# ramp_generator.net
KiCad netlist of a schematic drawn in Altium Designer
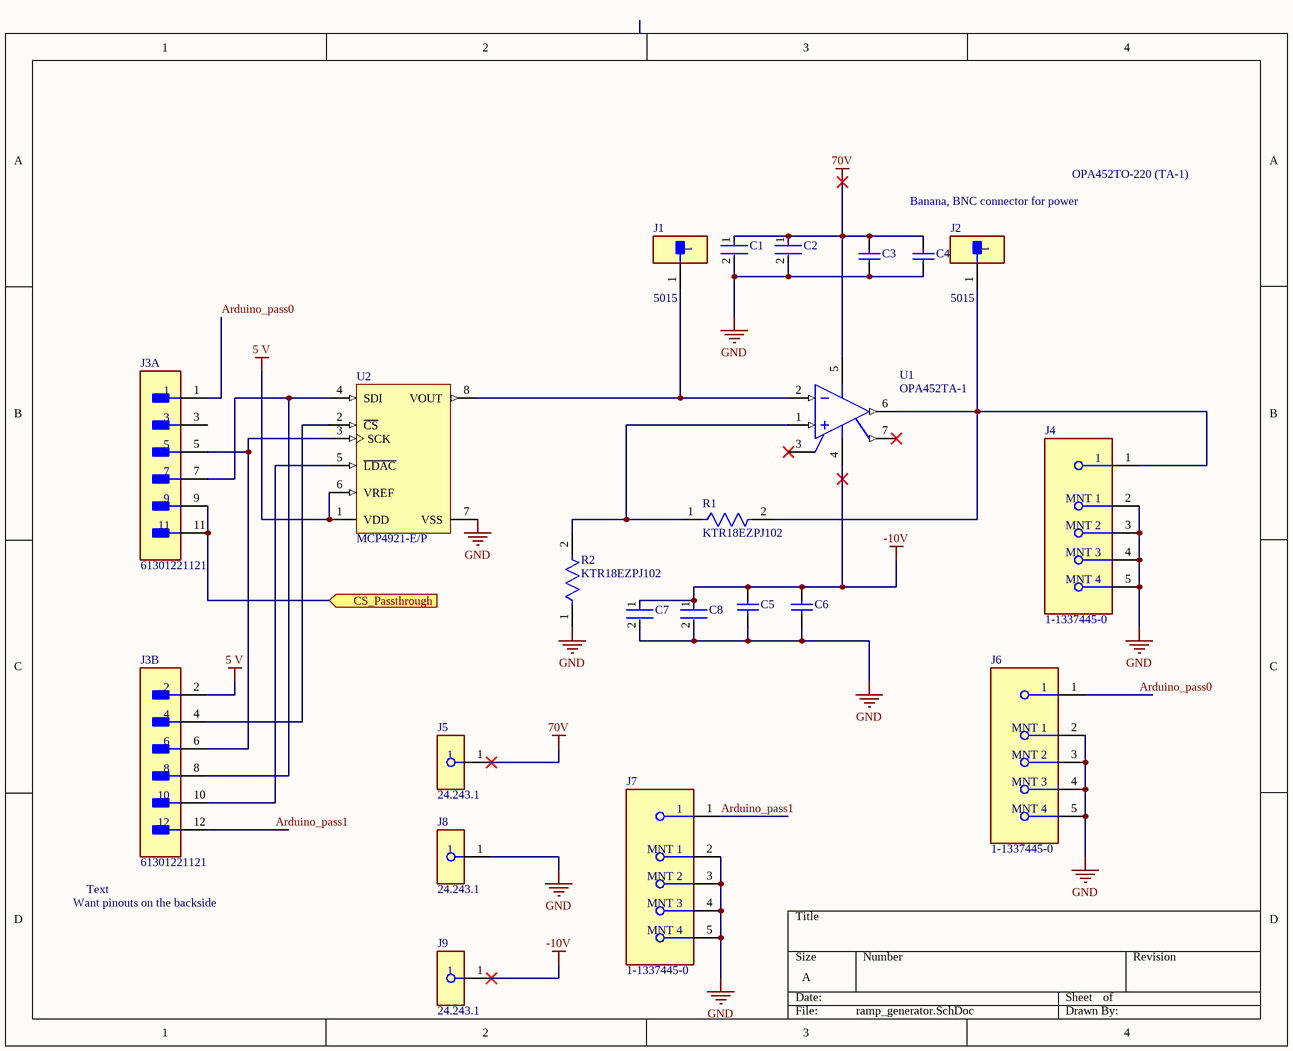
[diagram p0: ramp_generator.SchDoc]

(export (version "E")
  (design (tool "Eeschema 10.0.6"))
  (components
    (comp (ref "C1")
      (value "C3216JB1A106M160AA")
      (footprint "FP-C3216-160-0_2-IPC_C")
      (description "Multilayer Ceramic Capacitors 10uF ±20% 10V JB SMD 1206")
      (fields (field (name "TOLERANCE") "20%"))
      (libsource (lib "Altium Content Vault") (part "11868f565c42a9108669ba33697ecf6"))
    )
    (comp (ref "C2")
      (value "C3216JB1A106M160AA")
      (footprint "FP-C3216-160-0_2-IPC_C")
      (description "Multilayer Ceramic Capacitors 10uF ±20% 10V JB SMD 1206")
      (fields (field (name "TOLERANCE") "20%"))
      (libsource (lib "Altium Content Vault") (part "11868f565c42a9108669ba33697ecf6"))
    )
    (comp (ref "C3")
      (value "CAP 100pF 100V 1206(3216)")
      (footprint "CAPC1206(3216)100_N")
      (description "CAP 100pF 100V ±1% 1206 (3216 Metric) Thickness 1mm SMD")
      (fields (field (name "TOLERANCE") "Â±1%"))
      (libsource (lib "Altium Content Vault") (part "CAP"))
    )
    (comp (ref "C4")
      (value "CAP 100pF 100V 1206(3216)")
      (footprint "CAPC1206(3216)100_N")
      (description "CAP 100pF 100V ±1% 1206 (3216 Metric) Thickness 1mm SMD")
      (fields (field (name "TOLERANCE") "Â±1%"))
      (libsource (lib "Altium Content Vault") (part "CAP"))
    )
    (comp (ref "C5")
      (value "CAP 100pF 100V 1206(3216)")
      (footprint "CAPC1206(3216)100_N")
      (description "CAP 100pF 100V ±1% 1206 (3216 Metric) Thickness 1mm SMD")
      (fields (field (name "TOLERANCE") "Â±1%"))
      (libsource (lib "Altium Content Vault") (part "CAP"))
    )
    (comp (ref "C6")
      (value "CAP 100pF 100V 1206(3216)")
      (footprint "CAPC1206(3216)100_N")
      (description "CAP 100pF 100V ±1% 1206 (3216 Metric) Thickness 1mm SMD")
      (fields (field (name "TOLERANCE") "Â±1%"))
      (libsource (lib "Altium Content Vault") (part "CAP"))
    )
    (comp (ref "C7")
      (value "C3216JB1A106M160AA")
      (footprint "FP-C3216-160-0_2-IPC_C")
      (description "Multilayer Ceramic Capacitors 10uF ±20% 10V JB SMD 1206")
      (fields (field (name "TOLERANCE") "20%"))
      (libsource (lib "Altium Content Vault") (part "11868f565c42a9108669ba33697ecf6"))
    )
    (comp (ref "C8")
      (value "C3216JB1A106M160AA")
      (footprint "FP-C3216-160-0_2-IPC_C")
      (description "Multilayer Ceramic Capacitors 10uF ±20% 10V JB SMD 1206")
      (fields (field (name "TOLERANCE") "20%"))
      (libsource (lib "Altium Content Vault") (part "11868f565c42a9108669ba33697ecf6"))
    )
    (comp (ref "J1")
      (value "5015")
      (footprint "FP-5015-MFG")
      (description "PC TEST POINT MINIATURE")
      (fields
        (field (name "MANUFACTURER") "keystone")
        (field (name "OCTOPART") "https://octopart.com/5015-keystone-3822")
      )
      (libsource (lib "Altium Content Vault") (part "dd45045ce8184df9e99e12baf3f412c"))
    )
    (comp (ref "J2")
      (value "5015")
      (footprint "FP-5015-MFG")
      (description "PC TEST POINT MINIATURE")
      (fields
        (field (name "MANUFACTURER") "keystone")
        (field (name "OCTOPART") "https://octopart.com/5015-keystone-3822")
      )
      (libsource (lib "Altium Content Vault") (part "dd45045ce8184df9e99e12baf3f412c"))
    )
    (comp (ref "J3")
      (value "61301221121")
      (footprint "FP-61301221121-MFG")
      (description "CONN HEADER VERT 12POS 2.54MM")
      (libsource (lib "Altium Content Vault") (part "803cea653fbe7ecf087c1bc3cef566d"))
    )
    (comp (ref "J4")
      (value "1-1337445-0")
      (footprint "FP-1-1337445-0-MFG")
      (description "CONN BNC JACK STR 50 OHM PCB")
      (libsource (lib "Altium Content Vault") (part "c65b8a639cdaef1819ea20b5466f8fa"))
    )
    (comp (ref "J5")
      (value "24.243.1")
      (footprint "FP-24_243_1-MFG")
      (description "Banana Test Connector, 4mm, Socket, PCB Mount, 24 A, 60 VDC, Silver Plated Contacts, Green")
      (libsource (lib "Altium Content Vault") (part "98815daf2f2c152b0c43f5ab9800df6"))
    )
    (comp (ref "J6")
      (value "1-1337445-0")
      (footprint "FP-1-1337445-0-MFG")
      (description "CONN BNC JACK STR 50 OHM PCB")
      (libsource (lib "Altium Content Vault") (part "c65b8a639cdaef1819ea20b5466f8fa"))
    )
    (comp (ref "J7")
      (value "1-1337445-0")
      (footprint "FP-1-1337445-0-MFG")
      (description "CONN BNC JACK STR 50 OHM PCB")
      (libsource (lib "Altium Content Vault") (part "c65b8a639cdaef1819ea20b5466f8fa"))
    )
    (comp (ref "J8")
      (value "24.243.1")
      (footprint "FP-24_243_1-MFG")
      (description "Banana Test Connector, 4mm, Socket, PCB Mount, 24 A, 60 VDC, Silver Plated Contacts, Green")
      (libsource (lib "Altium Content Vault") (part "98815daf2f2c152b0c43f5ab9800df6"))
    )
    (comp (ref "J9")
      (value "24.243.1")
      (footprint "FP-24_243_1-MFG")
      (description "Banana Test Connector, 4mm, Socket, PCB Mount, 24 A, 60 VDC, Silver Plated Contacts, Green")
      (libsource (lib "Altium Content Vault") (part "98815daf2f2c152b0c43f5ab9800df6"))
    )
    (comp (ref "R1")
      (value "KTR18EZPJ102")
      (footprint "FP-KTR18-IPC_A")
      (description "Res Thick Film 1206 1kΩ 5% 0.1W ±200ppm/°C Automotive Paper T/R")
      (fields (field (name "TOLERANCE") "5%"))
      (libsource (lib "Altium Content Vault") (part "1029c3af85768c4190bb7ad29bc67b5"))
    )
    (comp (ref "R2")
      (value "KTR18EZPJ102")
      (footprint "FP-KTR18-IPC_A")
      (description "Res Thick Film 1206 1kΩ 5% 0.1W ±200ppm/°C Automotive Paper T/R")
      (fields (field (name "TOLERANCE") "5%"))
      (libsource (lib "Altium Content Vault") (part "1029c3af85768c4190bb7ad29bc67b5"))
    )
    (comp (ref "U1")
      (value "OPA452TA-1")
      (footprint "KVT0007A")
      (description "Operational Amplifier, 20 to 80 V, -40 to 125 degC, 7-pin FM (KVT7), Green (RoHS & no Sb/Br)")
      (fields (field (name "MANUFACTURER") "Texas Instruments"))
      (libsource (lib "Altium Content Vault") (part "TI-OPA452_453-7"))
    )
    (comp (ref "U2")
      (value "MCP4921-E/P")
      (footprint "PDIP300-P8")
      (description "12-Bit DAC with SPI Interface, 8-Pin PDIP, Extended Temperature")
      (libsource (lib "Altium Content Vault") (part "CON-DAC-MCP4921-8"))
    )
  )
  (nets
    (net (code "1") (name "-10V") (class "Default")
      (node (ref "C5") (pin "2") (pinfunction "2_2") (pintype "passive"))
      (node (ref "C6") (pin "1") (pinfunction "1_1") (pintype "passive"))
      (node (ref "C7") (pin "1") (pinfunction "1_1") (pintype "passive"))
      (node (ref "C8") (pin "1") (pinfunction "1_1") (pintype "passive"))
      (node (ref "J9") (pin "1") (pinfunction "1_1") (pintype "passive"))
      (node (ref "U1") (pin "4") (pinfunction "V-_4") (pintype "power_in"))
    )
    (net (code "2") (name "/Arduino_pass0") (class "Default")
      (node (ref "J3") (pin "1") (pinfunction "1_1") (pintype "passive"))
      (node (ref "J6") (pin "1") (pinfunction "1_1") (pintype "passive"))
    )
    (net (code "3") (name "/Arduino_pass1") (class "Default")
      (node (ref "J3") (pin "12") (pinfunction "12_12") (pintype "passive"))
      (node (ref "J7") (pin "1") (pinfunction "1_1") (pintype "passive"))
    )
    (net (code "4") (name "/CS_Passthrough") (class "Default")
      (node (ref "J3") (pin "11") (pinfunction "11_11") (pintype "passive"))
      (node (ref "J3") (pin "9") (pinfunction "9_9") (pintype "passive"))
    )
    (net (code "5") (name "5 V") (class "Default")
      (node (ref "J3") (pin "2") (pinfunction "2_2") (pintype "passive"))
      (node (ref "U2") (pin "1") (pinfunction "VDD_1") (pintype "power_in"))
      (node (ref "U2") (pin "6") (pinfunction "VREF_6") (pintype "input"))
    )
    (net (code "6") (name "70V") (class "Default")
      (node (ref "C1") (pin "1") (pinfunction "1_1") (pintype "passive"))
      (node (ref "C2") (pin "1") (pinfunction "1_1") (pintype "passive"))
      (node (ref "C3") (pin "2") (pinfunction "2_2") (pintype "passive"))
      (node (ref "C4") (pin "2") (pinfunction "2_2") (pintype "passive"))
      (node (ref "J5") (pin "1") (pinfunction "1_1") (pintype "passive"))
      (node (ref "U1") (pin "5") (pinfunction "V+_5") (pintype "power_in"))
    )
    (net (code "7") (name "GND") (class "Default")
      (node (ref "C1") (pin "2") (pinfunction "2_2") (pintype "passive"))
      (node (ref "C2") (pin "2") (pinfunction "2_2") (pintype "passive"))
      (node (ref "C3") (pin "1") (pinfunction "1_1") (pintype "passive"))
      (node (ref "C4") (pin "1") (pinfunction "1_1") (pintype "passive"))
      (node (ref "C5") (pin "1") (pinfunction "1_1") (pintype "passive"))
      (node (ref "C6") (pin "2") (pinfunction "2_2") (pintype "passive"))
      (node (ref "C7") (pin "2") (pinfunction "2_2") (pintype "passive"))
      (node (ref "C8") (pin "2") (pinfunction "2_2") (pintype "passive"))
      (node (ref "J4") (pin "2") (pinfunction "MNT_1_2") (pintype "passive"))
      (node (ref "J4") (pin "3") (pinfunction "MNT_2_3") (pintype "passive"))
      (node (ref "J4") (pin "4") (pinfunction "MNT_3_4") (pintype "passive"))
      (node (ref "J4") (pin "5") (pinfunction "MNT_4_5") (pintype "passive"))
      (node (ref "J6") (pin "2") (pinfunction "MNT_1_2") (pintype "passive"))
      (node (ref "J6") (pin "3") (pinfunction "MNT_2_3") (pintype "passive"))
      (node (ref "J6") (pin "4") (pinfunction "MNT_3_4") (pintype "passive"))
      (node (ref "J6") (pin "5") (pinfunction "MNT_4_5") (pintype "passive"))
      (node (ref "J7") (pin "2") (pinfunction "MNT_1_2") (pintype "passive"))
      (node (ref "J7") (pin "3") (pinfunction "MNT_2_3") (pintype "passive"))
      (node (ref "J7") (pin "4") (pinfunction "MNT_3_4") (pintype "passive"))
      (node (ref "J7") (pin "5") (pinfunction "MNT_4_5") (pintype "passive"))
      (node (ref "J8") (pin "1") (pinfunction "1_1") (pintype "passive"))
      (node (ref "R2") (pin "1") (pinfunction "1_1") (pintype "passive"))
      (node (ref "U2") (pin "7") (pinfunction "VSS_7") (pintype "power_in"))
    )
    (net (code "8") (name "Net-(U1-VIN+)") (class "Default")
      (node (ref "R1") (pin "1") (pinfunction "1_1") (pintype "passive"))
      (node (ref "R2") (pin "2") (pinfunction "2_2") (pintype "passive"))
      (node (ref "U1") (pin "1") (pinfunction "VIN+_1") (pintype "input"))
    )
    (net (code "9") (name "Net-(U1-VIN-)") (class "Default")
      (node (ref "J1") (pin "1") (pinfunction "1_1") (pintype "passive"))
      (node (ref "U1") (pin "2") (pinfunction "VIN-_2") (pintype "input"))
      (node (ref "U2") (pin "8") (pinfunction "VOUT_8") (pintype "output"))
    )
    (net (code "10") (name "Net-(U1-VO)") (class "Default")
      (node (ref "J2") (pin "1") (pinfunction "1_1") (pintype "passive"))
      (node (ref "J4") (pin "1") (pinfunction "1_1") (pintype "passive"))
      (node (ref "R1") (pin "2") (pinfunction "2_2") (pintype "passive"))
      (node (ref "U1") (pin "6") (pinfunction "VO_6") (pintype "output"))
    )
    (net (code "11") (name "Net-(U2-SCK)") (class "Default")
      (node (ref "J3") (pin "5") (pinfunction "5_5") (pintype "passive"))
      (node (ref "J3") (pin "6") (pinfunction "6_6") (pintype "passive"))
      (node (ref "U2") (pin "3") (pinfunction "SCK_3") (pintype "input"))
    )
    (net (code "12") (name "Net-(U2-SDI)") (class "Default")
      (node (ref "J3") (pin "7") (pinfunction "7_7") (pintype "passive"))
      (node (ref "J3") (pin "8") (pinfunction "8_8") (pintype "passive"))
      (node (ref "U2") (pin "4") (pinfunction "SDI_4") (pintype "input"))
    )
    (net (code "13") (name "Net-(U2-~{CS})") (class "Default")
      (node (ref "J3") (pin "4") (pinfunction "4_4") (pintype "passive"))
      (node (ref "U2") (pin "2") (pinfunction "~{CS}_2") (pintype "input"))
    )
    (net (code "14") (name "Net-(U2-~{LDAC})") (class "Default")
      (node (ref "J3") (pin "10") (pinfunction "10_10") (pintype "passive"))
      (node (ref "U2") (pin "5") (pinfunction "~{LDAC}_5") (pintype "input"))
    )
    (net (code "15") (name "unconnected-(J3-Pad3)") (class "Default")
      (node (ref "J3") (pin "3") (pinfunction "3_3") (pintype "passive"))
    )
    (net (code "16") (name "unconnected-(U1-FLAG-Pad7)") (class "Default")
      (node (ref "U1") (pin "7") (pinfunction "FLAG_7") (pintype "output+no_connect"))
    )
    (net (code "17") (name "unconnected-(U1-NC-Pad3)") (class "Default")
      (node (ref "U1") (pin "3") (pinfunction "NC_3") (pintype "passive+no_connect"))
    )
  )
)
